# Banks.net
KiCad netlist of a schematic drawn in Altium Designer
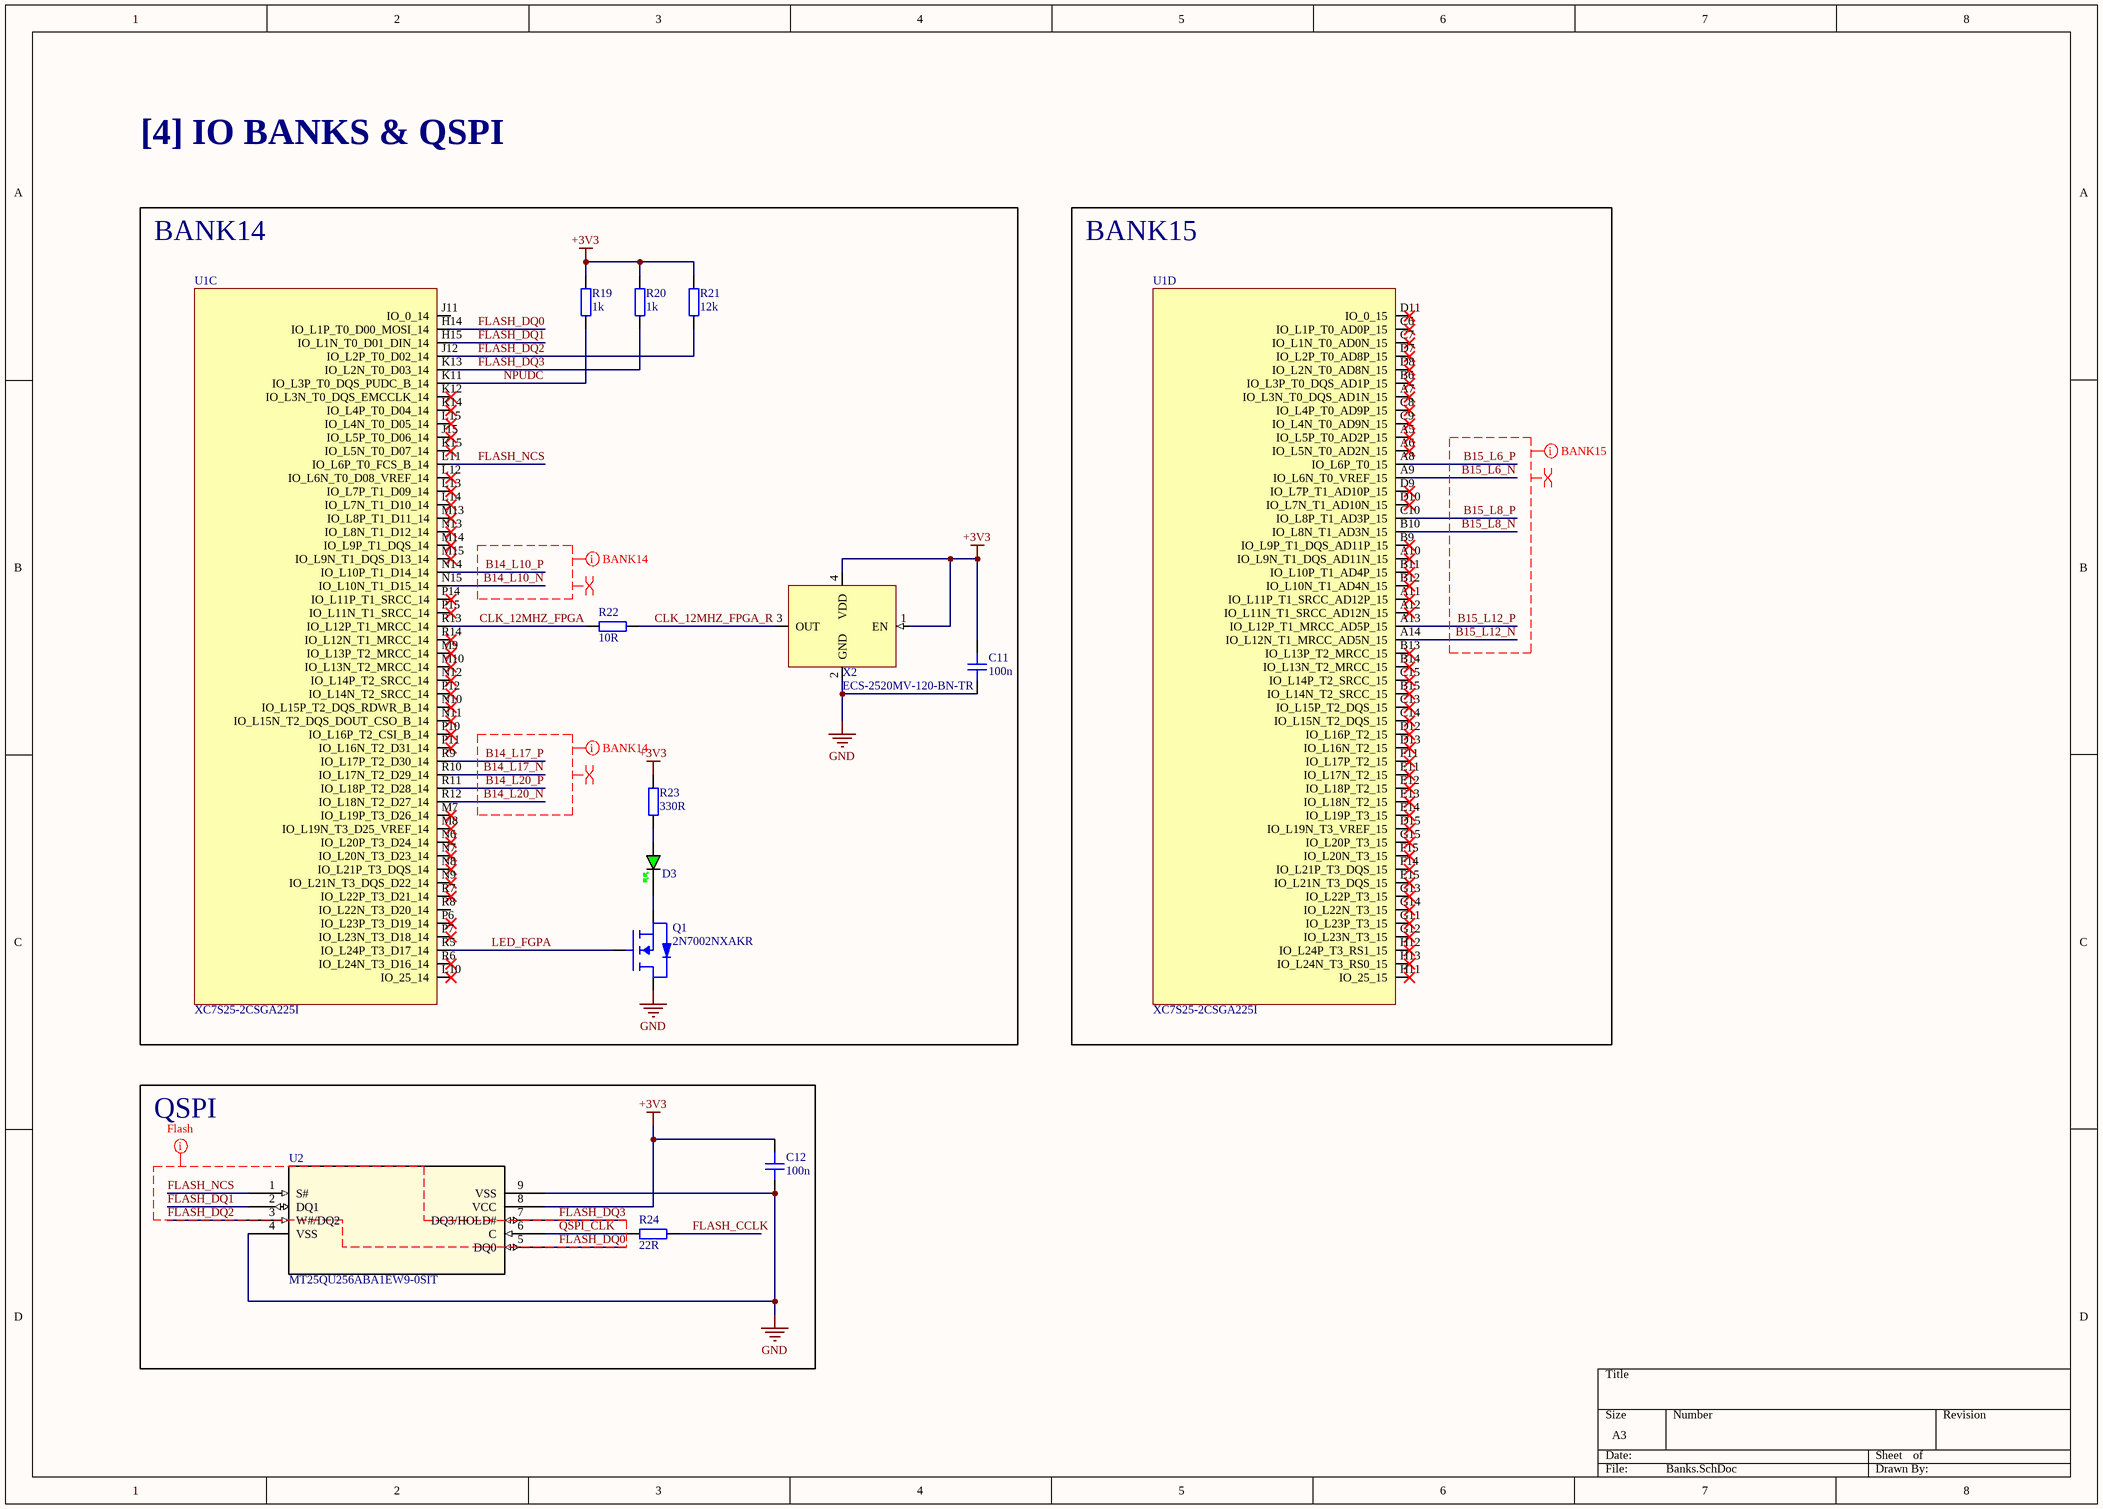
[diagram p0: Banks.SchDoc]

(export (version "E")
  (design (tool "Eeschema 10.0.6"))
  (components
    (comp (ref "C11")
      (value "100n")
      (footprint "CAP_0402")
      (description "Capacitor SMD 0402")
      (libsource (lib "Schematic-Lib-PhilsLab") (part "CAP_0402"))
    )
    (comp (ref "C12")
      (value "100n")
      (footprint "CAP_0402")
      (description "Capacitor SMD 0402")
      (libsource (lib "Schematic-Lib-PhilsLab") (part "CAP_0402"))
    )
    (comp (ref "D3")
      (value "GREEN")
      (footprint "LED_0402_GREEN")
      (description "LED 0402 GREEN SMD")
      (libsource (lib "Schematic-Lib-PhilsLab") (part "LED_0402_GREEN"))
    )
    (comp (ref "Q1")
      (value "2N7002NXAKR")
      (footprint "SSM3J338R,LF-SOT23-F")
      (description "MOSFET N-Channel Vds=60V Id=300mA with ESD Protection")
      (fields (field (name "MANUFACTURER") "Nexperia"))
      (libsource (lib "Schematic-Lib-PhilsLab") (part "2N7002NXAKR"))
    )
    (comp (ref "R19")
      (value "1k")
      (footprint "RES_0201")
      (description "Resistor SMD 0201")
      (libsource (lib "Schematic-Lib-PhilsLab") (part "RES_0201"))
    )
    (comp (ref "R20")
      (value "1k")
      (footprint "RES_0201")
      (description "Resistor SMD 0201")
      (libsource (lib "Schematic-Lib-PhilsLab") (part "RES_0201"))
    )
    (comp (ref "R21")
      (value "12k")
      (footprint "RES_0201")
      (description "Resistor SMD 0201")
      (libsource (lib "Schematic-Lib-PhilsLab") (part "RES_0201"))
    )
    (comp (ref "R22")
      (value "10R")
      (footprint "RES_0402")
      (description "Resistor SMD 0402")
      (libsource (lib "Schematic-Lib-PhilsLab") (part "RES_0402"))
    )
    (comp (ref "R23")
      (value "330R")
      (footprint "RES_0402")
      (description "Resistor SMD 0402")
      (libsource (lib "Schematic-Lib-PhilsLab") (part "RES_0402"))
    )
    (comp (ref "R24")
      (value "22R")
      (footprint "RES_0402")
      (description "Resistor SMD 0402")
      (libsource (lib "Schematic-Lib-PhilsLab") (part "RES_0402"))
    )
    (comp (ref "U1")
      (value "XC7S25-2CSGA225I")
      (footprint "CSGA225")
      (fields (field (name "MANUFACTURER") "Xilinx"))
      (libsource (lib "Schematic-Lib-PhilsLab") (part "XC7S25-2CSGA225I"))
    )
    (comp (ref "U2")
      (value "MT25QU256ABA1EW9-0SIT")
      (footprint "W-PDFN-8MLP8_8X6_MRN")
      (description "No Description Available")
      (libsource (lib "MT25QU256ABA1EW9-0SIT") (part "MT25QU256ABA1EW9-0SIT"))
    )
    (comp (ref "X2")
      (value "ECS-2520MV-120-BN-TR")
      (footprint "XTAL_2520")
      (fields
        (field (name "MANUFACTURER") "ECS")
        (field (name "MANUFACTURER PART NUMBER") "ECS-2520MV-130-BN-TR")
      )
      (libsource (lib "Schematic-Lib-PhilsLab") (part "ECS-2520MV-130-BN-TR"))
    )
  )
  (nets
    (net (code "1") (name "+3V3") (class "Default")
      (node (ref "C11") (pin "2") (pinfunction "2_2") (pintype "passive"))
      (node (ref "C12") (pin "2") (pinfunction "2_2") (pintype "passive"))
      (node (ref "R19") (pin "2") (pinfunction "2_2") (pintype "passive"))
      (node (ref "R20") (pin "2") (pinfunction "2_2") (pintype "passive"))
      (node (ref "R21") (pin "2") (pinfunction "2_2") (pintype "passive"))
      (node (ref "R23") (pin "2") (pinfunction "2_2") (pintype "passive"))
      (node (ref "U2") (pin "8") (pinfunction "VCC_8") (pintype "power_in"))
      (node (ref "X2") (pin "1") (pinfunction "EN_1") (pintype "input"))
      (node (ref "X2") (pin "4") (pinfunction "VDD_4") (pintype "power_in"))
    )
    (net (code "2") (name "/B14_L10_N") (class "Default")
      (node (ref "U1") (pin "N15") (pinfunction "IO_L10N_T1_D15_14_N15") (pintype "bidirectional"))
    )
    (net (code "3") (name "/B14_L10_P") (class "Default")
      (node (ref "U1") (pin "N14") (pinfunction "IO_L10P_T1_D14_14_N14") (pintype "bidirectional"))
    )
    (net (code "4") (name "/B14_L17_N") (class "Default")
      (node (ref "U1") (pin "R10") (pinfunction "IO_L17N_T2_D29_14_R10") (pintype "bidirectional"))
    )
    (net (code "5") (name "/B14_L17_P") (class "Default")
      (node (ref "U1") (pin "R9") (pinfunction "IO_L17P_T2_D30_14_R9") (pintype "bidirectional"))
    )
    (net (code "6") (name "/B14_L20_N") (class "Default")
      (node (ref "U1") (pin "R12") (pinfunction "IO_L18N_T2_D27_14_R12") (pintype "bidirectional"))
    )
    (net (code "7") (name "/B14_L20_P") (class "Default")
      (node (ref "U1") (pin "R11") (pinfunction "IO_L18P_T2_D28_14_R11") (pintype "bidirectional"))
    )
    (net (code "8") (name "/B15_L6_N") (class "Default")
      (node (ref "U1") (pin "A9") (pinfunction "IO_L6N_T0_VREF_15_A9") (pintype "bidirectional"))
    )
    (net (code "9") (name "/B15_L6_P") (class "Default")
      (node (ref "U1") (pin "A8") (pinfunction "IO_L6P_T0_15_A8") (pintype "bidirectional"))
    )
    (net (code "10") (name "/B15_L8_N") (class "Default")
      (node (ref "U1") (pin "B10") (pinfunction "IO_L8N_T1_AD3N_15_B10") (pintype "bidirectional"))
    )
    (net (code "11") (name "/B15_L8_P") (class "Default")
      (node (ref "U1") (pin "C10") (pinfunction "IO_L8P_T1_AD3P_15_C10") (pintype "bidirectional"))
    )
    (net (code "12") (name "/B15_L12_N") (class "Default")
      (node (ref "U1") (pin "A14") (pinfunction "IO_L12N_T1_MRCC_AD5N_15_A14") (pintype "bidirectional"))
    )
    (net (code "13") (name "/B15_L12_P") (class "Default")
      (node (ref "U1") (pin "A13") (pinfunction "IO_L12P_T1_MRCC_AD5P_15_A13") (pintype "bidirectional"))
    )
    (net (code "14") (name "/CLK_12MHZ_FPGA") (class "Default")
      (node (ref "R22") (pin "2") (pinfunction "2_2") (pintype "passive"))
      (node (ref "U1") (pin "R13") (pinfunction "IO_L12P_T1_MRCC_14_R13") (pintype "bidirectional"))
    )
    (net (code "15") (name "/CLK_12MHZ_FPGA_R") (class "Default")
      (node (ref "R22") (pin "1") (pinfunction "1_1") (pintype "passive"))
      (node (ref "X2") (pin "3") (pinfunction "OUT_3") (pintype "passive"))
    )
    (net (code "16") (name "/FLASH_CCLK") (class "Default")
      (node (ref "R24") (pin "2") (pinfunction "2_2") (pintype "passive"))
    )
    (net (code "17") (name "/FLASH_DQ0") (class "Default")
      (node (ref "U1") (pin "H14") (pinfunction "IO_L1P_T0_D00_MOSI_14_H14") (pintype "bidirectional"))
      (node (ref "U2") (pin "5") (pinfunction "DQ0_5") (pintype "bidirectional"))
    )
    (net (code "18") (name "/FLASH_DQ1") (class "Default")
      (node (ref "U1") (pin "H15") (pinfunction "IO_L1N_T0_D01_DIN_14_H15") (pintype "bidirectional"))
      (node (ref "U2") (pin "2") (pinfunction "DQ1_2") (pintype "bidirectional"))
    )
    (net (code "19") (name "/FLASH_DQ2") (class "Default")
      (node (ref "R21") (pin "1") (pinfunction "1_1") (pintype "passive"))
      (node (ref "U1") (pin "J12") (pinfunction "IO_L2P_T0_D02_14_J12") (pintype "bidirectional"))
      (node (ref "U2") (pin "3") (pinfunction "W#/DQ2_3") (pintype "input"))
    )
    (net (code "20") (name "/FLASH_DQ3") (class "Default")
      (node (ref "R20") (pin "1") (pinfunction "1_1") (pintype "passive"))
      (node (ref "U1") (pin "K13") (pinfunction "IO_L2N_T0_D03_14_K13") (pintype "bidirectional"))
      (node (ref "U2") (pin "7") (pinfunction "DQ3/HOLD#_7") (pintype "bidirectional"))
    )
    (net (code "21") (name "/FLASH_NCS") (class "Default")
      (node (ref "U1") (pin "L11") (pinfunction "IO_L6P_T0_FCS_B_14_L11") (pintype "bidirectional"))
      (node (ref "U2") (pin "1") (pinfunction "S#_1") (pintype "input"))
    )
    (net (code "22") (name "/LED_FGPA") (class "Default")
      (node (ref "Q1") (pin "G") (pinfunction "G_G") (pintype "passive"))
      (node (ref "U1") (pin "R5") (pinfunction "IO_L24P_T3_D17_14_R5") (pintype "bidirectional"))
    )
    (net (code "23") (name "/NPUDC") (class "Default")
      (node (ref "R19") (pin "1") (pinfunction "1_1") (pintype "passive"))
      (node (ref "U1") (pin "K11") (pinfunction "IO_L3P_T0_DQS_PUDC_B_14_K11") (pintype "bidirectional"))
    )
    (net (code "24") (name "/QSPI_CLK") (class "Default")
      (node (ref "R24") (pin "1") (pinfunction "1_1") (pintype "passive"))
      (node (ref "U2") (pin "6") (pinfunction "C_6") (pintype "input"))
    )
    (net (code "25") (name "GND") (class "Default")
      (node (ref "C11") (pin "1") (pinfunction "1_1") (pintype "passive"))
      (node (ref "C12") (pin "1") (pinfunction "1_1") (pintype "passive"))
      (node (ref "Q1") (pin "D") (pinfunction "D_D") (pintype "passive"))
      (node (ref "U2") (pin "4") (pinfunction "VSS_4") (pintype "power_in"))
      (node (ref "U2") (pin "9") (pinfunction "VSS_9") (pintype "power_in"))
      (node (ref "X2") (pin "2") (pinfunction "GND_2") (pintype "power_in"))
    )
    (net (code "26") (name "Net-(D3-PadA)") (class "Default")
      (node (ref "D3") (pin "A") (pinfunction "A_A") (pintype "passive"))
      (node (ref "R23") (pin "1") (pinfunction "1_1") (pintype "passive"))
    )
    (net (code "27") (name "Net-(D3-PadK)") (class "Default")
      (node (ref "D3") (pin "K") (pinfunction "K_K") (pintype "passive"))
      (node (ref "Q1") (pin "S") (pinfunction "S_S") (pintype "passive"))
    )
    (net (code "28") (name "unconnected-(U1C-IO_0_14-PadJ11)") (class "Default")
      (node (ref "U1") (pin "J11") (pinfunction "IO_0_14_J11") (pintype "bidirectional"))
    )
    (net (code "29") (name "unconnected-(U1C-IO_25_14-PadL10)") (class "Default")
      (node (ref "U1") (pin "L10") (pinfunction "IO_25_14_L10") (pintype "bidirectional+no_connect"))
    )
    (net (code "30") (name "unconnected-(U1C-IO_L3N_T0_DQS_EMCCLK_14-PadK12)") (class "Default")
      (node (ref "U1") (pin "K12") (pinfunction "IO_L3N_T0_DQS_EMCCLK_14_K12") (pintype "bidirectional+no_connect"))
    )
    (net (code "31") (name "unconnected-(U1C-IO_L4N_T0_D05_14-PadL15)") (class "Default")
      (node (ref "U1") (pin "L15") (pinfunction "IO_L4N_T0_D05_14_L15") (pintype "bidirectional+no_connect"))
    )
    (net (code "32") (name "unconnected-(U1C-IO_L4P_T0_D04_14-PadK14)") (class "Default")
      (node (ref "U1") (pin "K14") (pinfunction "IO_L4P_T0_D04_14_K14") (pintype "bidirectional+no_connect"))
    )
    (net (code "33") (name "unconnected-(U1C-IO_L5N_T0_D07_14-PadK15)") (class "Default")
      (node (ref "U1") (pin "K15") (pinfunction "IO_L5N_T0_D07_14_K15") (pintype "bidirectional+no_connect"))
    )
    (net (code "34") (name "unconnected-(U1C-IO_L5P_T0_D06_14-PadJ15)") (class "Default")
      (node (ref "U1") (pin "J15") (pinfunction "IO_L5P_T0_D06_14_J15") (pintype "bidirectional+no_connect"))
    )
    (net (code "35") (name "unconnected-(U1C-IO_L6N_T0_D08_VREF_14-PadL12)") (class "Default")
      (node (ref "U1") (pin "L12") (pinfunction "IO_L6N_T0_D08_VREF_14_L12") (pintype "bidirectional+no_connect"))
    )
    (net (code "36") (name "unconnected-(U1C-IO_L7N_T1_D10_14-PadL14)") (class "Default")
      (node (ref "U1") (pin "L14") (pinfunction "IO_L7N_T1_D10_14_L14") (pintype "bidirectional+no_connect"))
    )
    (net (code "37") (name "unconnected-(U1C-IO_L7P_T1_D09_14-PadL13)") (class "Default")
      (node (ref "U1") (pin "L13") (pinfunction "IO_L7P_T1_D09_14_L13") (pintype "bidirectional+no_connect"))
    )
    (net (code "38") (name "unconnected-(U1C-IO_L8N_T1_D12_14-PadN13)") (class "Default")
      (node (ref "U1") (pin "N13") (pinfunction "IO_L8N_T1_D12_14_N13") (pintype "bidirectional+no_connect"))
    )
    (net (code "39") (name "unconnected-(U1C-IO_L8P_T1_D11_14-PadM13)") (class "Default")
      (node (ref "U1") (pin "M13") (pinfunction "IO_L8P_T1_D11_14_M13") (pintype "bidirectional+no_connect"))
    )
    (net (code "40") (name "unconnected-(U1C-IO_L9N_T1_DQS_D13_14-PadM15)") (class "Default")
      (node (ref "U1") (pin "M15") (pinfunction "IO_L9N_T1_DQS_D13_14_M15") (pintype "bidirectional+no_connect"))
    )
    (net (code "41") (name "unconnected-(U1C-IO_L9P_T1_DQS_14-PadM14)") (class "Default")
      (node (ref "U1") (pin "M14") (pinfunction "IO_L9P_T1_DQS_14_M14") (pintype "bidirectional+no_connect"))
    )
    (net (code "42") (name "unconnected-(U1C-IO_L11N_T1_SRCC_14-PadP15)") (class "Default")
      (node (ref "U1") (pin "P15") (pinfunction "IO_L11N_T1_SRCC_14_P15") (pintype "bidirectional+no_connect"))
    )
    (net (code "43") (name "unconnected-(U1C-IO_L11P_T1_SRCC_14-PadP14)") (class "Default")
      (node (ref "U1") (pin "P14") (pinfunction "IO_L11P_T1_SRCC_14_P14") (pintype "bidirectional+no_connect"))
    )
    (net (code "44") (name "unconnected-(U1C-IO_L12N_T1_MRCC_14-PadR14)") (class "Default")
      (node (ref "U1") (pin "R14") (pinfunction "IO_L12N_T1_MRCC_14_R14") (pintype "bidirectional+no_connect"))
    )
    (net (code "45") (name "unconnected-(U1C-IO_L13N_T2_MRCC_14-PadM10)") (class "Default")
      (node (ref "U1") (pin "M10") (pinfunction "IO_L13N_T2_MRCC_14_M10") (pintype "bidirectional+no_connect"))
    )
    (net (code "46") (name "unconnected-(U1C-IO_L13P_T2_MRCC_14-PadM9)") (class "Default")
      (node (ref "U1") (pin "M9") (pinfunction "IO_L13P_T2_MRCC_14_M9") (pintype "bidirectional+no_connect"))
    )
    (net (code "47") (name "unconnected-(U1C-IO_L14N_T2_SRCC_14-PadP12)") (class "Default")
      (node (ref "U1") (pin "P12") (pinfunction "IO_L14N_T2_SRCC_14_P12") (pintype "bidirectional+no_connect"))
    )
    (net (code "48") (name "unconnected-(U1C-IO_L14P_T2_SRCC_14-PadN12)") (class "Default")
      (node (ref "U1") (pin "N12") (pinfunction "IO_L14P_T2_SRCC_14_N12") (pintype "bidirectional+no_connect"))
    )
    (net (code "49") (name "unconnected-(U1C-IO_L15N_T2_DQS_DOUT_CSO_B_14-PadN11)") (class "Default")
      (node (ref "U1") (pin "N11") (pinfunction "IO_L15N_T2_DQS_DOUT_CSO_B_14_N11") (pintype "bidirectional+no_connect"))
    )
    (net (code "50") (name "unconnected-(U1C-IO_L15P_T2_DQS_RDWR_B_14-PadN10)") (class "Default")
      (node (ref "U1") (pin "N10") (pinfunction "IO_L15P_T2_DQS_RDWR_B_14_N10") (pintype "bidirectional+no_connect"))
    )
    (net (code "51") (name "unconnected-(U1C-IO_L16N_T2_D31_14-PadP11)") (class "Default")
      (node (ref "U1") (pin "P11") (pinfunction "IO_L16N_T2_D31_14_P11") (pintype "bidirectional+no_connect"))
    )
    (net (code "52") (name "unconnected-(U1C-IO_L16P_T2_CSI_B_14-PadP10)") (class "Default")
      (node (ref "U1") (pin "P10") (pinfunction "IO_L16P_T2_CSI_B_14_P10") (pintype "bidirectional+no_connect"))
    )
    (net (code "53") (name "unconnected-(U1C-IO_L19N_T3_D25_VREF_14-PadM8)") (class "Default")
      (node (ref "U1") (pin "M8") (pinfunction "IO_L19N_T3_D25_VREF_14_M8") (pintype "bidirectional+no_connect"))
    )
    (net (code "54") (name "unconnected-(U1C-IO_L19P_T3_D26_14-PadM7)") (class "Default")
      (node (ref "U1") (pin "M7") (pinfunction "IO_L19P_T3_D26_14_M7") (pintype "bidirectional+no_connect"))
    )
    (net (code "55") (name "unconnected-(U1C-IO_L20N_T3_D23_14-PadN7)") (class "Default")
      (node (ref "U1") (pin "N7") (pinfunction "IO_L20N_T3_D23_14_N7") (pintype "bidirectional+no_connect"))
    )
    (net (code "56") (name "unconnected-(U1C-IO_L20P_T3_D24_14-PadN6)") (class "Default")
      (node (ref "U1") (pin "N6") (pinfunction "IO_L20P_T3_D24_14_N6") (pintype "bidirectional+no_connect"))
    )
    (net (code "57") (name "unconnected-(U1C-IO_L21N_T3_DQS_D22_14-PadN9)") (class "Default")
      (node (ref "U1") (pin "N9") (pinfunction "IO_L21N_T3_DQS_D22_14_N9") (pintype "bidirectional+no_connect"))
    )
    (net (code "58") (name "unconnected-(U1C-IO_L21P_T3_DQS_14-PadN8)") (class "Default")
      (node (ref "U1") (pin "N8") (pinfunction "IO_L21P_T3_DQS_14_N8") (pintype "bidirectional+no_connect"))
    )
    (net (code "59") (name "unconnected-(U1C-IO_L22N_T3_D20_14-PadR8)") (class "Default")
      (node (ref "U1") (pin "R8") (pinfunction "IO_L22N_T3_D20_14_R8") (pintype "bidirectional"))
    )
    (net (code "60") (name "unconnected-(U1C-IO_L22P_T3_D21_14-PadR7)") (class "Default")
      (node (ref "U1") (pin "R7") (pinfunction "IO_L22P_T3_D21_14_R7") (pintype "bidirectional+no_connect"))
    )
    (net (code "61") (name "unconnected-(U1C-IO_L23N_T3_D18_14-PadP7)") (class "Default")
      (node (ref "U1") (pin "P7") (pinfunction "IO_L23N_T3_D18_14_P7") (pintype "bidirectional+no_connect"))
    )
    (net (code "62") (name "unconnected-(U1C-IO_L23P_T3_D19_14-PadP6)") (class "Default")
      (node (ref "U1") (pin "P6") (pinfunction "IO_L23P_T3_D19_14_P6") (pintype "bidirectional+no_connect"))
    )
    (net (code "63") (name "unconnected-(U1C-IO_L24N_T3_D16_14-PadR6)") (class "Default")
      (node (ref "U1") (pin "R6") (pinfunction "IO_L24N_T3_D16_14_R6") (pintype "bidirectional+no_connect"))
    )
    (net (code "64") (name "unconnected-(U1D-IO_0_15-PadD11)") (class "Default")
      (node (ref "U1") (pin "D11") (pinfunction "IO_0_15_D11") (pintype "bidirectional+no_connect"))
    )
    (net (code "65") (name "unconnected-(U1D-IO_25_15-PadH11)") (class "Default")
      (node (ref "U1") (pin "H11") (pinfunction "IO_25_15_H11") (pintype "bidirectional+no_connect"))
    )
    (net (code "66") (name "unconnected-(U1D-IO_L1N_T0_AD0N_15-PadC7)") (class "Default")
      (node (ref "U1") (pin "C7") (pinfunction "IO_L1N_T0_AD0N_15_C7") (pintype "bidirectional+no_connect"))
    )
    (net (code "67") (name "unconnected-(U1D-IO_L1P_T0_AD0P_15-PadC6)") (class "Default")
      (node (ref "U1") (pin "C6") (pinfunction "IO_L1P_T0_AD0P_15_C6") (pintype "bidirectional+no_connect"))
    )
    (net (code "68") (name "unconnected-(U1D-IO_L2N_T0_AD8N_15-PadD8)") (class "Default")
      (node (ref "U1") (pin "D8") (pinfunction "IO_L2N_T0_AD8N_15_D8") (pintype "bidirectional+no_connect"))
    )
    (net (code "69") (name "unconnected-(U1D-IO_L2P_T0_AD8P_15-PadD7)") (class "Default")
      (node (ref "U1") (pin "D7") (pinfunction "IO_L2P_T0_AD8P_15_D7") (pintype "bidirectional+no_connect"))
    )
    (net (code "70") (name "unconnected-(U1D-IO_L3N_T0_DQS_AD1N_15-PadA7)") (class "Default")
      (node (ref "U1") (pin "A7") (pinfunction "IO_L3N_T0_DQS_AD1N_15_A7") (pintype "bidirectional+no_connect"))
    )
    (net (code "71") (name "unconnected-(U1D-IO_L3P_T0_DQS_AD1P_15-PadB6)") (class "Default")
      (node (ref "U1") (pin "B6") (pinfunction "IO_L3P_T0_DQS_AD1P_15_B6") (pintype "bidirectional+no_connect"))
    )
    (net (code "72") (name "unconnected-(U1D-IO_L4N_T0_AD9N_15-PadC9)") (class "Default")
      (node (ref "U1") (pin "C9") (pinfunction "IO_L4N_T0_AD9N_15_C9") (pintype "bidirectional+no_connect"))
    )
    (net (code "73") (name "unconnected-(U1D-IO_L4P_T0_AD9P_15-PadC8)") (class "Default")
      (node (ref "U1") (pin "C8") (pinfunction "IO_L4P_T0_AD9P_15_C8") (pintype "bidirectional+no_connect"))
    )
    (net (code "74") (name "unconnected-(U1D-IO_L5N_T0_AD2N_15-PadA6)") (class "Default")
      (node (ref "U1") (pin "A6") (pinfunction "IO_L5N_T0_AD2N_15_A6") (pintype "bidirectional+no_connect"))
    )
    (net (code "75") (name "unconnected-(U1D-IO_L5P_T0_AD2P_15-PadA5)") (class "Default")
      (node (ref "U1") (pin "A5") (pinfunction "IO_L5P_T0_AD2P_15_A5") (pintype "bidirectional+no_connect"))
    )
    (net (code "76") (name "unconnected-(U1D-IO_L7N_T1_AD10N_15-PadD10)") (class "Default")
      (node (ref "U1") (pin "D10") (pinfunction "IO_L7N_T1_AD10N_15_D10") (pintype "bidirectional+no_connect"))
    )
    (net (code "77") (name "unconnected-(U1D-IO_L7P_T1_AD10P_15-PadD9)") (class "Default")
      (node (ref "U1") (pin "D9") (pinfunction "IO_L7P_T1_AD10P_15_D9") (pintype "bidirectional+no_connect"))
    )
    (net (code "78") (name "unconnected-(U1D-IO_L9N_T1_DQS_AD11N_15-PadA10)") (class "Default")
      (node (ref "U1") (pin "A10") (pinfunction "IO_L9N_T1_DQS_AD11N_15_A10") (pintype "bidirectional+no_connect"))
    )
    (net (code "79") (name "unconnected-(U1D-IO_L9P_T1_DQS_AD11P_15-PadB9)") (class "Default")
      (node (ref "U1") (pin "B9") (pinfunction "IO_L9P_T1_DQS_AD11P_15_B9") (pintype "bidirectional+no_connect"))
    )
    (net (code "80") (name "unconnected-(U1D-IO_L10N_T1_AD4N_15-PadB12)") (class "Default")
      (node (ref "U1") (pin "B12") (pinfunction "IO_L10N_T1_AD4N_15_B12") (pintype "bidirectional+no_connect"))
    )
    (net (code "81") (name "unconnected-(U1D-IO_L10P_T1_AD4P_15-PadB11)") (class "Default")
      (node (ref "U1") (pin "B11") (pinfunction "IO_L10P_T1_AD4P_15_B11") (pintype "bidirectional+no_connect"))
    )
    (net (code "82") (name "unconnected-(U1D-IO_L11N_T1_SRCC_AD12N_15-PadA12)") (class "Default")
      (node (ref "U1") (pin "A12") (pinfunction "IO_L11N_T1_SRCC_AD12N_15_A12") (pintype "bidirectional+no_connect"))
    )
    (net (code "83") (name "unconnected-(U1D-IO_L11P_T1_SRCC_AD12P_15-PadA11)") (class "Default")
      (node (ref "U1") (pin "A11") (pinfunction "IO_L11P_T1_SRCC_AD12P_15_A11") (pintype "bidirectional+no_connect"))
    )
    (net (code "84") (name "unconnected-(U1D-IO_L13N_T2_MRCC_15-PadB14)") (class "Default")
      (node (ref "U1") (pin "B14") (pinfunction "IO_L13N_T2_MRCC_15_B14") (pintype "bidirectional+no_connect"))
    )
    (net (code "85") (name "unconnected-(U1D-IO_L13P_T2_MRCC_15-PadB13)") (class "Default")
      (node (ref "U1") (pin "B13") (pinfunction "IO_L13P_T2_MRCC_15_B13") (pintype "bidirectional+no_connect"))
    )
    (net (code "86") (name "unconnected-(U1D-IO_L14N_T2_SRCC_15-PadB15)") (class "Default")
      (node (ref "U1") (pin "B15") (pinfunction "IO_L14N_T2_SRCC_15_B15") (pintype "bidirectional+no_connect"))
    )
    (net (code "87") (name "unconnected-(U1D-IO_L14P_T2_SRCC_15-PadC15)") (class "Default")
      (node (ref "U1") (pin "C15") (pinfunction "IO_L14P_T2_SRCC_15_C15") (pintype "bidirectional+no_connect"))
    )
    (net (code "88") (name "unconnected-(U1D-IO_L15N_T2_DQS_15-PadC14)") (class "Default")
      (node (ref "U1") (pin "C14") (pinfunction "IO_L15N_T2_DQS_15_C14") (pintype "bidirectional+no_connect"))
    )
    (net (code "89") (name "unconnected-(U1D-IO_L15P_T2_DQS_15-PadC13)") (class "Default")
      (node (ref "U1") (pin "C13") (pinfunction "IO_L15P_T2_DQS_15_C13") (pintype "bidirectional+no_connect"))
    )
    (net (code "90") (name "unconnected-(U1D-IO_L16N_T2_15-PadD13)") (class "Default")
      (node (ref "U1") (pin "D13") (pinfunction "IO_L16N_T2_15_D13") (pintype "bidirectional+no_connect"))
    )
    (net (code "91") (name "unconnected-(U1D-IO_L16P_T2_15-PadD12)") (class "Default")
      (node (ref "U1") (pin "D12") (pinfunction "IO_L16P_T2_15_D12") (pintype "bidirectional+no_connect"))
    )
    (net (code "92") (name "unconnected-(U1D-IO_L17N_T2_15-PadE11)") (class "Default")
      (node (ref "U1") (pin "E11") (pinfunction "IO_L17N_T2_15_E11") (pintype "bidirectional+no_connect"))
    )
    (net (code "93") (name "unconnected-(U1D-IO_L17P_T2_15-PadF11)") (class "Default")
      (node (ref "U1") (pin "F11") (pinfunction "IO_L17P_T2_15_F11") (pintype "bidirectional+no_connect"))
    )
    (net (code "94") (name "unconnected-(U1D-IO_L18N_T2_15-PadE13)") (class "Default")
      (node (ref "U1") (pin "E13") (pinfunction "IO_L18N_T2_15_E13") (pintype "bidirectional+no_connect"))
    )
    (net (code "95") (name "unconnected-(U1D-IO_L18P_T2_15-PadE12)") (class "Default")
      (node (ref "U1") (pin "E12") (pinfunction "IO_L18P_T2_15_E12") (pintype "bidirectional+no_connect"))
    )
    (net (code "96") (name "unconnected-(U1D-IO_L19N_T3_VREF_15-PadD15)") (class "Default")
      (node (ref "U1") (pin "D15") (pinfunction "IO_L19N_T3_VREF_15_D15") (pintype "bidirectional+no_connect"))
    )
    (net (code "97") (name "unconnected-(U1D-IO_L19P_T3_15-PadE14)") (class "Default")
      (node (ref "U1") (pin "E14") (pinfunction "IO_L19P_T3_15_E14") (pintype "bidirectional+no_connect"))
    )
    (net (code "98") (name "unconnected-(U1D-IO_L20N_T3_15-PadF15)") (class "Default")
      (node (ref "U1") (pin "F15") (pinfunction "IO_L20N_T3_15_F15") (pintype "bidirectional+no_connect"))
    )
    (net (code "99") (name "unconnected-(U1D-IO_L20P_T3_15-PadG15)") (class "Default")
      (node (ref "U1") (pin "G15") (pinfunction "IO_L20P_T3_15_G15") (pintype "bidirectional+no_connect"))
    )
    (net (code "100") (name "unconnected-(U1D-IO_L21N_T3_DQS_15-PadE15)") (class "Default")
      (node (ref "U1") (pin "E15") (pinfunction "IO_L21N_T3_DQS_15_E15") (pintype "bidirectional+no_connect"))
    )
    (net (code "101") (name "unconnected-(U1D-IO_L21P_T3_DQS_15-PadF14)") (class "Default")
      (node (ref "U1") (pin "F14") (pinfunction "IO_L21P_T3_DQS_15_F14") (pintype "bidirectional+no_connect"))
    )
    (net (code "102") (name "unconnected-(U1D-IO_L22N_T3_15-PadG14)") (class "Default")
      (node (ref "U1") (pin "G14") (pinfunction "IO_L22N_T3_15_G14") (pintype "bidirectional+no_connect"))
    )
    (net (code "103") (name "unconnected-(U1D-IO_L22P_T3_15-PadG13)") (class "Default")
      (node (ref "U1") (pin "G13") (pinfunction "IO_L22P_T3_15_G13") (pintype "bidirectional+no_connect"))
    )
    (net (code "104") (name "unconnected-(U1D-IO_L23N_T3_15-PadG12)") (class "Default")
      (node (ref "U1") (pin "G12") (pinfunction "IO_L23N_T3_15_G12") (pintype "bidirectional+no_connect"))
    )
    (net (code "105") (name "unconnected-(U1D-IO_L23P_T3_15-PadG11)") (class "Default")
      (node (ref "U1") (pin "G11") (pinfunction "IO_L23P_T3_15_G11") (pintype "bidirectional+no_connect"))
    )
    (net (code "106") (name "unconnected-(U1D-IO_L24N_T3_RS0_15-PadH13)") (class "Default")
      (node (ref "U1") (pin "H13") (pinfunction "IO_L24N_T3_RS0_15_H13") (pintype "bidirectional+no_connect"))
    )
    (net (code "107") (name "unconnected-(U1D-IO_L24P_T3_RS1_15-PadH12)") (class "Default")
      (node (ref "U1") (pin "H12") (pinfunction "IO_L24P_T3_RS1_15_H12") (pintype "bidirectional+no_connect"))
    )
  )
)
